# INA3221.net
KiCad netlist of a schematic drawn in EAGLE
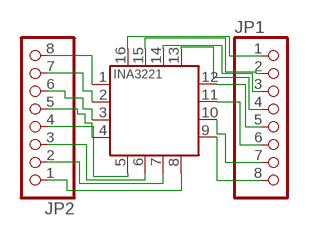
[diagram p0: schematic, sheet 1]

(export (version "E")
  (design (tool "Eeschema 10.0.6"))
  (components
    (comp (ref "JP1")
      (value "PINHD-1X8BIG")
      (footprint "eagle-import:1X08-BIG")
      (libsource (lib "eagle-import") (part "PINHD-1X8BIG"))
    )
    (comp (ref "JP2")
      (value "PINHD-1X8BIG")
      (footprint "eagle-import:1X08-BIG")
      (libsource (lib "eagle-import") (part "PINHD-1X8BIG"))
    )
    (comp (ref "U1")
      (value "INA3221.")
      (footprint "eagle-import:HVQFN16_4X4")
      (libsource (lib "eagle-import") (part "INA3221."))
    )
  )
  (nets
    (net (code "1") (name "Net-(U1-A0)") (class "Default")
      (node (ref "JP2") (pin "4") (pinfunction "4_4") (pintype "passive"))
      (node (ref "U1") (pin "5") (pinfunction "A0_5") (pintype "input"))
    )
    (net (code "2") (name "Net-(U1-CRITICAL)") (class "Default")
      (node (ref "JP1") (pin "8") (pinfunction "8_8") (pintype "passive"))
      (node (ref "U1") (pin "9") (pinfunction "CRITICAL_9") (pintype "output"))
    )
    (net (code "3") (name "Net-(U1-GND)") (class "Default")
      (node (ref "JP2") (pin "6") (pinfunction "6_6") (pintype "passive"))
      (node (ref "U1") (pin "3") (pinfunction "GND_3") (pintype "power_in"))
    )
    (net (code "4") (name "Net-(U1-IN+1)") (class "Default")
      (node (ref "JP1") (pin "5") (pinfunction "5_5") (pintype "passive"))
      (node (ref "U1") (pin "12") (pinfunction "IN+1_12") (pintype "input"))
    )
    (net (code "5") (name "Net-(U1-IN+2)") (class "Default")
      (node (ref "JP1") (pin "2") (pinfunction "2_2") (pintype "passive"))
      (node (ref "U1") (pin "15") (pinfunction "IN+2_15") (pintype "input"))
    )
    (net (code "6") (name "Net-(U1-IN+3)") (class "Default")
      (node (ref "JP2") (pin "7") (pinfunction "7_7") (pintype "passive"))
      (node (ref "U1") (pin "2") (pinfunction "IN+3_2") (pintype "input"))
    )
    (net (code "7") (name "Net-(U1-IN-1)") (class "Default")
      (node (ref "JP1") (pin "6") (pinfunction "6_6") (pintype "passive"))
      (node (ref "U1") (pin "11") (pinfunction "IN-1_11") (pintype "input"))
    )
    (net (code "8") (name "Net-(U1-IN-2)") (class "Default")
      (node (ref "JP1") (pin "3") (pinfunction "3_3") (pintype "passive"))
      (node (ref "U1") (pin "14") (pinfunction "IN-2_14") (pintype "input"))
    )
    (net (code "9") (name "Net-(U1-IN-3)") (class "Default")
      (node (ref "JP2") (pin "8") (pinfunction "8_8") (pintype "passive"))
      (node (ref "U1") (pin "1") (pinfunction "IN-3_1") (pintype "input"))
    )
    (net (code "10") (name "Net-(U1-PV)") (class "Default")
      (node (ref "JP1") (pin "7") (pinfunction "7_7") (pintype "passive"))
      (node (ref "U1") (pin "10") (pinfunction "PV_10") (pintype "output"))
    )
    (net (code "11") (name "Net-(U1-SCL)") (class "Default")
      (node (ref "JP2") (pin "3") (pinfunction "3_3") (pintype "passive"))
      (node (ref "U1") (pin "6") (pinfunction "SCL_6") (pintype "input"))
    )
    (net (code "12") (name "Net-(U1-SDA)") (class "Default")
      (node (ref "JP2") (pin "2") (pinfunction "2_2") (pintype "passive"))
      (node (ref "U1") (pin "7") (pinfunction "SDA_7") (pintype "bidirectional"))
    )
    (net (code "13") (name "Net-(U1-TC)") (class "Default")
      (node (ref "JP1") (pin "4") (pinfunction "4_4") (pintype "passive"))
      (node (ref "U1") (pin "13") (pinfunction "TC_13") (pintype "output"))
    )
    (net (code "14") (name "Net-(U1-VPU)") (class "Default")
      (node (ref "JP1") (pin "1") (pinfunction "1_1") (pintype "passive"))
      (node (ref "U1") (pin "16") (pinfunction "VPU_16") (pintype "input"))
    )
    (net (code "15") (name "Net-(U1-VS)") (class "Default")
      (node (ref "JP2") (pin "5") (pinfunction "5_5") (pintype "passive"))
      (node (ref "U1") (pin "4") (pinfunction "VS_4") (pintype "power_in"))
    )
    (net (code "16") (name "Net-(U1-WARNING)") (class "Default")
      (node (ref "JP2") (pin "1") (pinfunction "1_1") (pintype "passive"))
      (node (ref "U1") (pin "8") (pinfunction "WARNING_8") (pintype "output"))
    )
  )
)
